# LM7805_solutions.net
KiCad netlist of a schematic drawn in EAGLE
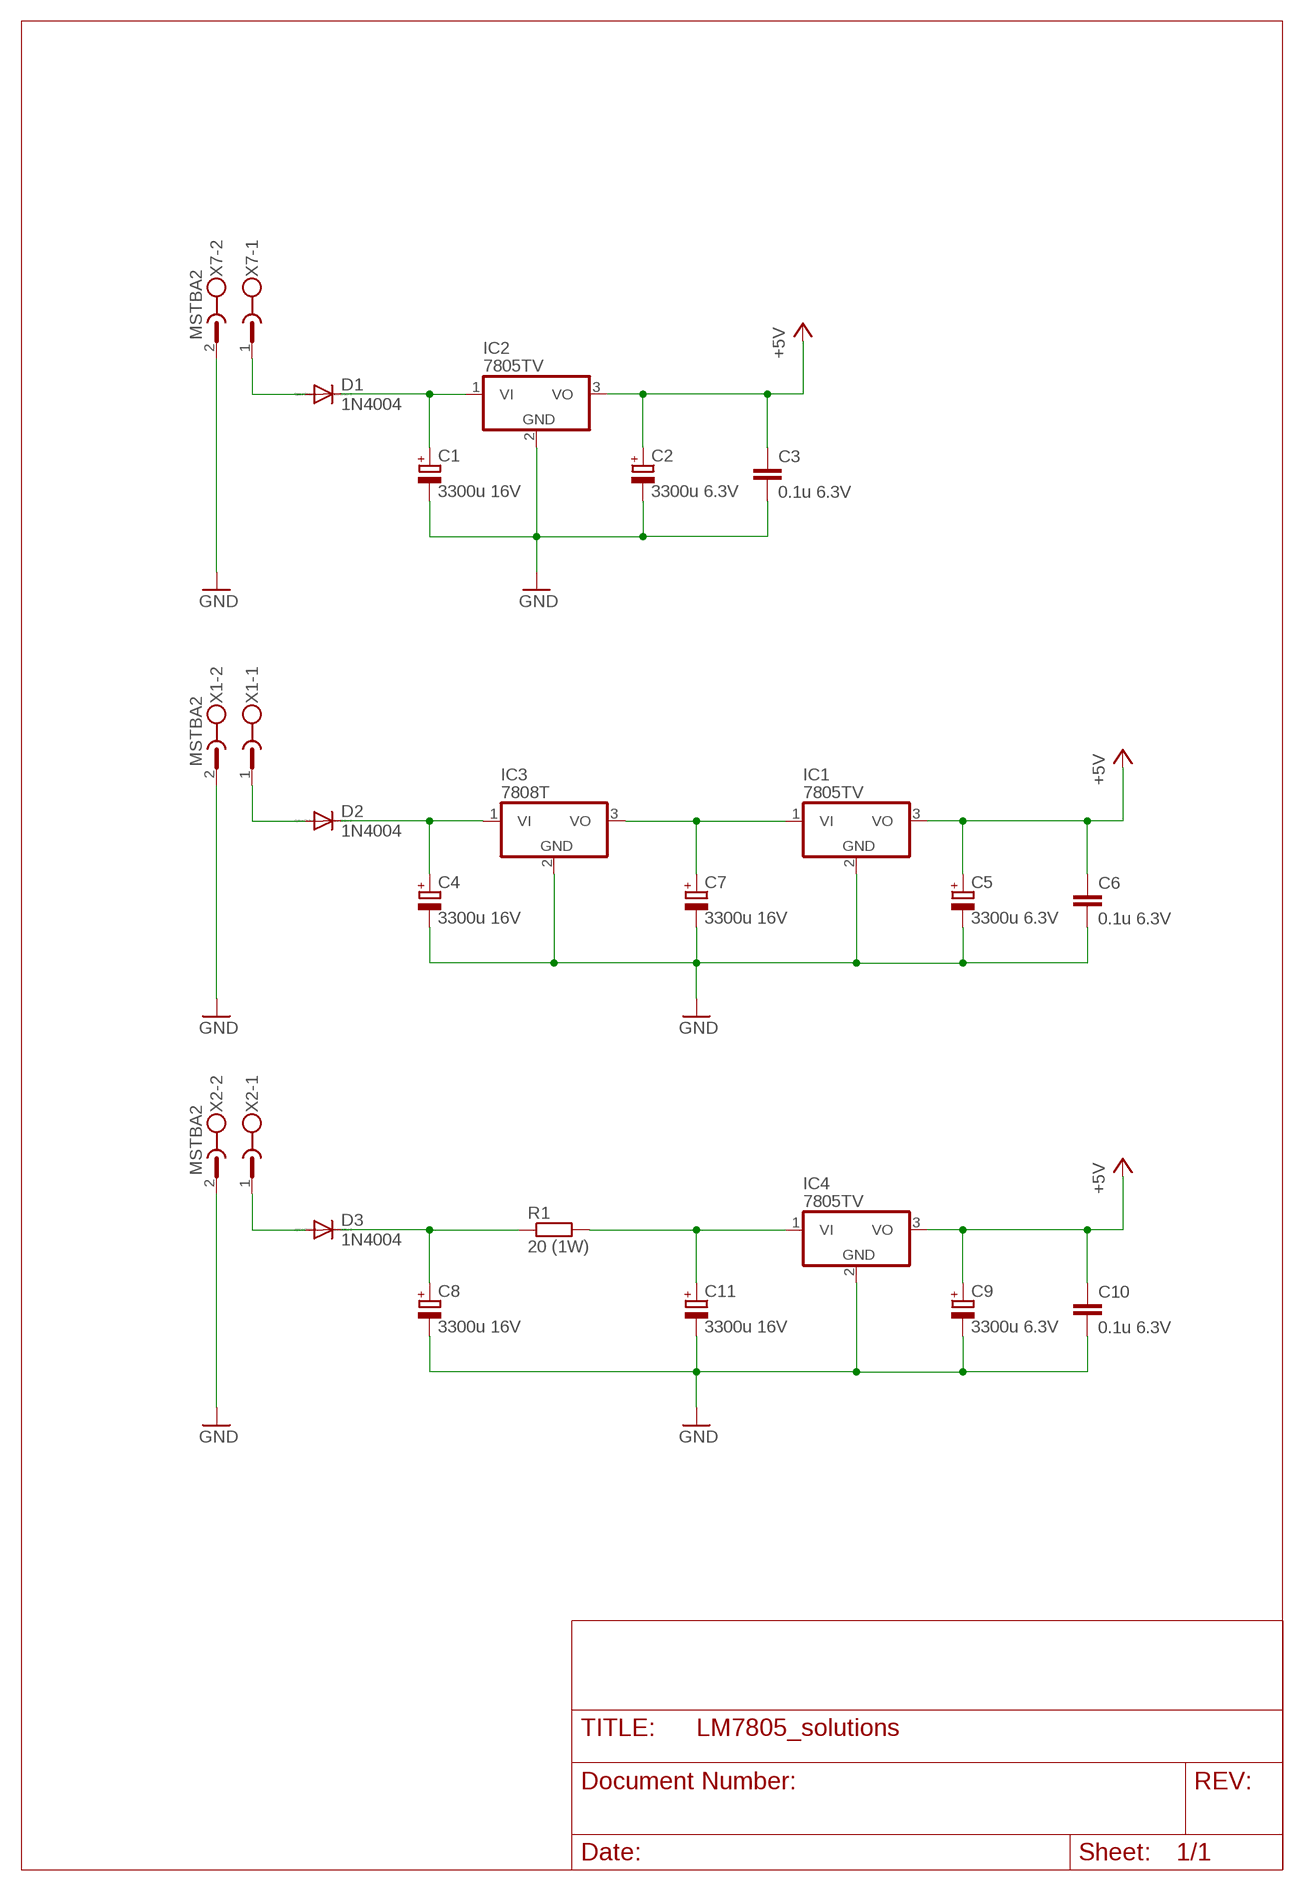
[diagram p0: schematic, sheet 1]

(export (version "E")
  (design (tool "Eeschema 10.0.6"))
  (components
    (comp (ref "C1")
      (value "3300u 16V")
      (footprint "eagle-import:EB20D")
      (libsource (lib "eagle-import") (part "CPOL-EUE10-20"))
    )
    (comp (ref "C2")
      (value "3300u 6.3V")
      (footprint "eagle-import:EB20D")
      (libsource (lib "eagle-import") (part "CPOL-EUE10-20"))
    )
    (comp (ref "C3")
      (value "0.1u 6.3V")
      (footprint "eagle-import:C050-030X075")
      (libsource (lib "eagle-import") (part "C-EU050-030X075"))
    )
    (comp (ref "C4")
      (value "3300u 16V")
      (footprint "eagle-import:EB20D")
      (libsource (lib "eagle-import") (part "CPOL-EUE10-20"))
    )
    (comp (ref "C5")
      (value "3300u 6.3V")
      (footprint "eagle-import:EB20D")
      (libsource (lib "eagle-import") (part "CPOL-EUE10-20"))
    )
    (comp (ref "C6")
      (value "0.1u 6.3V")
      (footprint "eagle-import:C050-030X075")
      (libsource (lib "eagle-import") (part "C-EU050-030X075"))
    )
    (comp (ref "C7")
      (value "3300u 16V")
      (footprint "eagle-import:EB20D")
      (libsource (lib "eagle-import") (part "CPOL-EUE10-20"))
    )
    (comp (ref "C8")
      (value "3300u 16V")
      (footprint "eagle-import:EB20D")
      (libsource (lib "eagle-import") (part "CPOL-EUE10-20"))
    )
    (comp (ref "C9")
      (value "3300u 6.3V")
      (footprint "eagle-import:EB20D")
      (libsource (lib "eagle-import") (part "CPOL-EUE10-20"))
    )
    (comp (ref "C10")
      (value "0.1u 6.3V")
      (footprint "eagle-import:C050-030X075")
      (libsource (lib "eagle-import") (part "C-EU050-030X075"))
    )
    (comp (ref "C11")
      (value "3300u 16V")
      (footprint "eagle-import:EB20D")
      (libsource (lib "eagle-import") (part "CPOL-EUE10-20"))
    )
    (comp (ref "D1")
      (value "1N4004")
      (footprint "eagle-import:DO41-10")
      (libsource (lib "eagle-import") (part "1N4004"))
    )
    (comp (ref "D2")
      (value "1N4004")
      (footprint "eagle-import:DO41-10")
      (libsource (lib "eagle-import") (part "1N4004"))
    )
    (comp (ref "D3")
      (value "1N4004")
      (footprint "eagle-import:DO41-10")
      (libsource (lib "eagle-import") (part "1N4004"))
    )
    (comp (ref "IC1")
      (value "7805TV")
      (footprint "eagle-import:TO220V")
      (libsource (lib "eagle-import") (part "78TV05"))
    )
    (comp (ref "IC2")
      (value "7805TV")
      (footprint "eagle-import:TO220V")
      (libsource (lib "eagle-import") (part "78TV05"))
    )
    (comp (ref "IC3")
      (value "7808T")
      (footprint "eagle-import:TO220H")
      (libsource (lib "eagle-import") (part "78T08"))
    )
    (comp (ref "IC4")
      (value "7805TV")
      (footprint "eagle-import:TO220V")
      (libsource (lib "eagle-import") (part "78TV05"))
    )
    (comp (ref "R1")
      (value "20 (1W)")
      (footprint "eagle-import:0411_15")
      (libsource (lib "eagle-import") (part "R-EU_0411/15"))
    )
    (comp (ref "X1")
      (value "MSTBA2")
      (footprint "eagle-import:MSTBA2")
      (fields (field (name "MF") "FARNELL") (field (name "MPN") "1757242"))
      (libsource (lib "eagle-import") (part "MSTBA2"))
    )
    (comp (ref "X2")
      (value "MSTBA2")
      (footprint "eagle-import:MSTBA2")
      (fields (field (name "MF") "FARNELL") (field (name "MPN") "1757242"))
      (libsource (lib "eagle-import") (part "MSTBA2"))
    )
    (comp (ref "X7")
      (value "MSTBA2")
      (footprint "eagle-import:MSTBA2")
      (fields (field (name "MF") "FARNELL") (field (name "MPN") "1757242"))
      (libsource (lib "eagle-import") (part "MSTBA2"))
    )
  )
  (nets
    (net (code "1") (name "+5V") (class "Default")
      (node (ref "C10") (pin "1") (pinfunction "1_1") (pintype "passive"))
      (node (ref "C2") (pin "+") (pinfunction "+_+") (pintype "passive"))
      (node (ref "C3") (pin "1") (pinfunction "1_1") (pintype "passive"))
      (node (ref "C5") (pin "+") (pinfunction "+_+") (pintype "passive"))
      (node (ref "C6") (pin "1") (pinfunction "1_1") (pintype "passive"))
      (node (ref "C9") (pin "+") (pinfunction "+_+") (pintype "passive"))
      (node (ref "IC1") (pin "3") (pinfunction "VO_3") (pintype "passive"))
      (node (ref "IC2") (pin "3") (pinfunction "VO_3") (pintype "passive"))
      (node (ref "IC4") (pin "3") (pinfunction "VO_3") (pintype "passive"))
    )
    (net (code "2") (name "GND") (class "Default")
      (node (ref "C1") (pin "-") (pinfunction "-_-") (pintype "passive"))
      (node (ref "C10") (pin "2") (pinfunction "2_2") (pintype "passive"))
      (node (ref "C11") (pin "-") (pinfunction "-_-") (pintype "passive"))
      (node (ref "C2") (pin "-") (pinfunction "-_-") (pintype "passive"))
      (node (ref "C3") (pin "2") (pinfunction "2_2") (pintype "passive"))
      (node (ref "C4") (pin "-") (pinfunction "-_-") (pintype "passive"))
      (node (ref "C5") (pin "-") (pinfunction "-_-") (pintype "passive"))
      (node (ref "C6") (pin "2") (pinfunction "2_2") (pintype "passive"))
      (node (ref "C7") (pin "-") (pinfunction "-_-") (pintype "passive"))
      (node (ref "C8") (pin "-") (pinfunction "-_-") (pintype "passive"))
      (node (ref "C9") (pin "-") (pinfunction "-_-") (pintype "passive"))
      (node (ref "IC1") (pin "2") (pinfunction "GND_2") (pintype "passive"))
      (node (ref "IC2") (pin "2") (pinfunction "GND_2") (pintype "passive"))
      (node (ref "IC3") (pin "2") (pinfunction "GND_2") (pintype "passive"))
      (node (ref "IC4") (pin "2") (pinfunction "GND_2") (pintype "passive"))
      (node (ref "X1") (pin "2") (pinfunction "1_2") (pintype "passive"))
      (node (ref "X2") (pin "2") (pinfunction "1_2") (pintype "passive"))
      (node (ref "X7") (pin "2") (pinfunction "1_2") (pintype "passive"))
    )
    (net (code "3") (name "Net-(C8-Pad+)") (class "Default")
      (node (ref "C8") (pin "+") (pinfunction "+_+") (pintype "passive"))
      (node (ref "D3") (pin "C") (pinfunction "C_C") (pintype "passive"))
      (node (ref "R1") (pin "1") (pinfunction "1_1") (pintype "passive"))
    )
    (net (code "4") (name "Net-(D1-PadA)") (class "Default")
      (node (ref "D1") (pin "A") (pinfunction "A_A") (pintype "passive"))
      (node (ref "X7") (pin "1") (pinfunction "1_1") (pintype "passive"))
    )
    (net (code "5") (name "Net-(D2-PadA)") (class "Default")
      (node (ref "D2") (pin "A") (pinfunction "A_A") (pintype "passive"))
      (node (ref "X1") (pin "1") (pinfunction "1_1") (pintype "passive"))
    )
    (net (code "6") (name "Net-(D3-PadA)") (class "Default")
      (node (ref "D3") (pin "A") (pinfunction "A_A") (pintype "passive"))
      (node (ref "X2") (pin "1") (pinfunction "1_1") (pintype "passive"))
    )
    (net (code "7") (name "Net-(IC1-VI)") (class "Default")
      (node (ref "C7") (pin "+") (pinfunction "+_+") (pintype "passive"))
      (node (ref "IC1") (pin "1") (pinfunction "VI_1") (pintype "input"))
      (node (ref "IC3") (pin "3") (pinfunction "VO_3") (pintype "passive"))
    )
    (net (code "8") (name "Net-(IC2-VI)") (class "Default")
      (node (ref "C1") (pin "+") (pinfunction "+_+") (pintype "passive"))
      (node (ref "D1") (pin "C") (pinfunction "C_C") (pintype "passive"))
      (node (ref "IC2") (pin "1") (pinfunction "VI_1") (pintype "input"))
    )
    (net (code "9") (name "Net-(IC3-VI)") (class "Default")
      (node (ref "C4") (pin "+") (pinfunction "+_+") (pintype "passive"))
      (node (ref "D2") (pin "C") (pinfunction "C_C") (pintype "passive"))
      (node (ref "IC3") (pin "1") (pinfunction "VI_1") (pintype "input"))
    )
    (net (code "10") (name "Net-(IC4-VI)") (class "Default")
      (node (ref "C11") (pin "+") (pinfunction "+_+") (pintype "passive"))
      (node (ref "IC4") (pin "1") (pinfunction "VI_1") (pintype "input"))
      (node (ref "R1") (pin "2") (pinfunction "2_2") (pintype "passive"))
    )
  )
)
